# PSIO_Switchboard_PU-8_v1.net
KiCad netlist of a schematic drawn in EAGLE
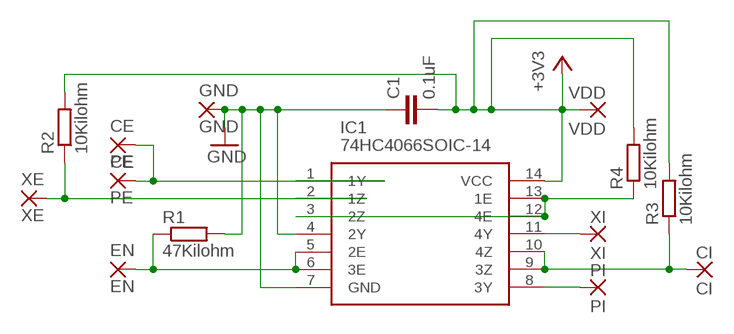
[diagram p0: schematic, sheet 1]

(export (version "E")
  (design (tool "Eeschema 10.0.6"))
  (components
    (comp (ref "C1")
      (value "0.1uF")
      (footprint "eagle-import:C0805")
      (libsource (lib "eagle-import") (part "CAPACITORSC0805"))
    )
    (comp (ref "CE")
      (value "CE")
      (footprint "eagle-import:CIRCLE-2X2")
      (libsource (lib "eagle-import") (part "PADSCIRCLE-2X2"))
    )
    (comp (ref "CI")
      (value "CI")
      (footprint "eagle-import:CIRCLE-2X2")
      (libsource (lib "eagle-import") (part "PADSCIRCLE-2X2"))
    )
    (comp (ref "EN")
      (value "EN")
      (footprint "eagle-import:CIRCLE-2X2")
      (libsource (lib "eagle-import") (part "PADSCIRCLE-2X2"))
    )
    (comp (ref "GND")
      (value "GND")
      (footprint "eagle-import:CIRCLE-2X2")
      (libsource (lib "eagle-import") (part "PADSCIRCLE-2X2"))
    )
    (comp (ref "IC1")
      (value "74HC4066SOIC-14")
      (footprint "eagle-import:SOIC-14")
      (libsource (lib "eagle-import") (part "74HC4066SOIC-14"))
    )
    (comp (ref "PE")
      (value "PE")
      (footprint "eagle-import:CIRCLE-2X2")
      (libsource (lib "eagle-import") (part "PADSCIRCLE-2X2"))
    )
    (comp (ref "PI")
      (value "PI")
      (footprint "eagle-import:CIRCLE-2X2")
      (libsource (lib "eagle-import") (part "PADSCIRCLE-2X2"))
    )
    (comp (ref "R1")
      (value "47Kilohm")
      (footprint "eagle-import:R0805")
      (libsource (lib "eagle-import") (part "RESISTORSR0805"))
    )
    (comp (ref "R2")
      (value "10Kilohm")
      (footprint "eagle-import:R0805")
      (libsource (lib "eagle-import") (part "RESISTORSR0805"))
    )
    (comp (ref "R3")
      (value "10Kilohm")
      (footprint "eagle-import:R0805")
      (libsource (lib "eagle-import") (part "RESISTORSR0805"))
    )
    (comp (ref "R4")
      (value "10Kilohm")
      (footprint "eagle-import:R0805")
      (libsource (lib "eagle-import") (part "RESISTORSR0805"))
    )
    (comp (ref "VDD")
      (value "VDD")
      (footprint "eagle-import:CIRCLE-2X2")
      (libsource (lib "eagle-import") (part "PADSCIRCLE-2X2"))
    )
    (comp (ref "XE")
      (value "XE")
      (footprint "eagle-import:CIRCLE-2X2")
      (libsource (lib "eagle-import") (part "PADSCIRCLE-2X2"))
    )
    (comp (ref "XI")
      (value "XI")
      (footprint "eagle-import:CIRCLE-2X2")
      (libsource (lib "eagle-import") (part "PADSCIRCLE-2X2"))
    )
  )
  (nets
    (net (code "1") (name "+3V3") (class "Default")
      (node (ref "C1") (pin "2") (pinfunction "2_2") (pintype "passive"))
      (node (ref "IC1") (pin "14") (pinfunction "VCC_14") (pintype "bidirectional"))
      (node (ref "R2") (pin "2") (pinfunction "2_2") (pintype "passive"))
      (node (ref "R3") (pin "2") (pinfunction "2_2") (pintype "passive"))
      (node (ref "R4") (pin "2") (pinfunction "2_2") (pintype "passive"))
      (node (ref "VDD") (pin "1") (pinfunction "P_1") (pintype "passive"))
    )
    (net (code "2") (name "GND") (class "Default")
      (node (ref "C1") (pin "1") (pinfunction "1_1") (pintype "passive"))
      (node (ref "GND") (pin "1") (pinfunction "P_1") (pintype "passive"))
      (node (ref "IC1") (pin "4") (pinfunction "2Y_4") (pintype "bidirectional"))
      (node (ref "IC1") (pin "7") (pinfunction "GND_7") (pintype "bidirectional"))
      (node (ref "R1") (pin "2") (pinfunction "2_2") (pintype "passive"))
    )
    (net (code "3") (name "Net-(CE-P)") (class "Default")
      (node (ref "CE") (pin "1") (pinfunction "P_1") (pintype "passive"))
      (node (ref "IC1") (pin "1") (pinfunction "1Y_1") (pintype "bidirectional"))
      (node (ref "PE") (pin "1") (pinfunction "P_1") (pintype "passive"))
    )
    (net (code "4") (name "Net-(CI-P)") (class "Default")
      (node (ref "CI") (pin "1") (pinfunction "P_1") (pintype "passive"))
      (node (ref "IC1") (pin "10") (pinfunction "4Z_10") (pintype "bidirectional"))
      (node (ref "IC1") (pin "9") (pinfunction "3Z_9") (pintype "bidirectional"))
      (node (ref "R3") (pin "1") (pinfunction "1_1") (pintype "passive"))
    )
    (net (code "5") (name "Net-(EN-P)") (class "Default")
      (node (ref "EN") (pin "1") (pinfunction "P_1") (pintype "passive"))
      (node (ref "IC1") (pin "5") (pinfunction "2E_5") (pintype "bidirectional"))
      (node (ref "IC1") (pin "6") (pinfunction "3E_6") (pintype "bidirectional"))
      (node (ref "R1") (pin "1") (pinfunction "1_1") (pintype "passive"))
    )
    (net (code "6") (name "Net-(IC1-1E)") (class "Default")
      (node (ref "IC1") (pin "12") (pinfunction "4E_12") (pintype "bidirectional"))
      (node (ref "IC1") (pin "13") (pinfunction "1E_13") (pintype "bidirectional"))
      (node (ref "IC1") (pin "3") (pinfunction "2Z_3") (pintype "bidirectional"))
      (node (ref "R4") (pin "1") (pinfunction "1_1") (pintype "passive"))
    )
    (net (code "7") (name "Net-(IC1-1Z)") (class "Default")
      (node (ref "IC1") (pin "2") (pinfunction "1Z_2") (pintype "bidirectional"))
      (node (ref "R2") (pin "1") (pinfunction "1_1") (pintype "passive"))
      (node (ref "XE") (pin "1") (pinfunction "P_1") (pintype "passive"))
    )
    (net (code "8") (name "Net-(IC1-3Y)") (class "Default")
      (node (ref "IC1") (pin "8") (pinfunction "3Y_8") (pintype "bidirectional"))
      (node (ref "PI") (pin "1") (pinfunction "P_1") (pintype "passive"))
    )
    (net (code "9") (name "Net-(IC1-4Y)") (class "Default")
      (node (ref "IC1") (pin "11") (pinfunction "4Y_11") (pintype "bidirectional"))
      (node (ref "XI") (pin "1") (pinfunction "P_1") (pintype "passive"))
    )
  )
)
